# Display.net
KiCad netlist of a schematic drawn in Altium Designer
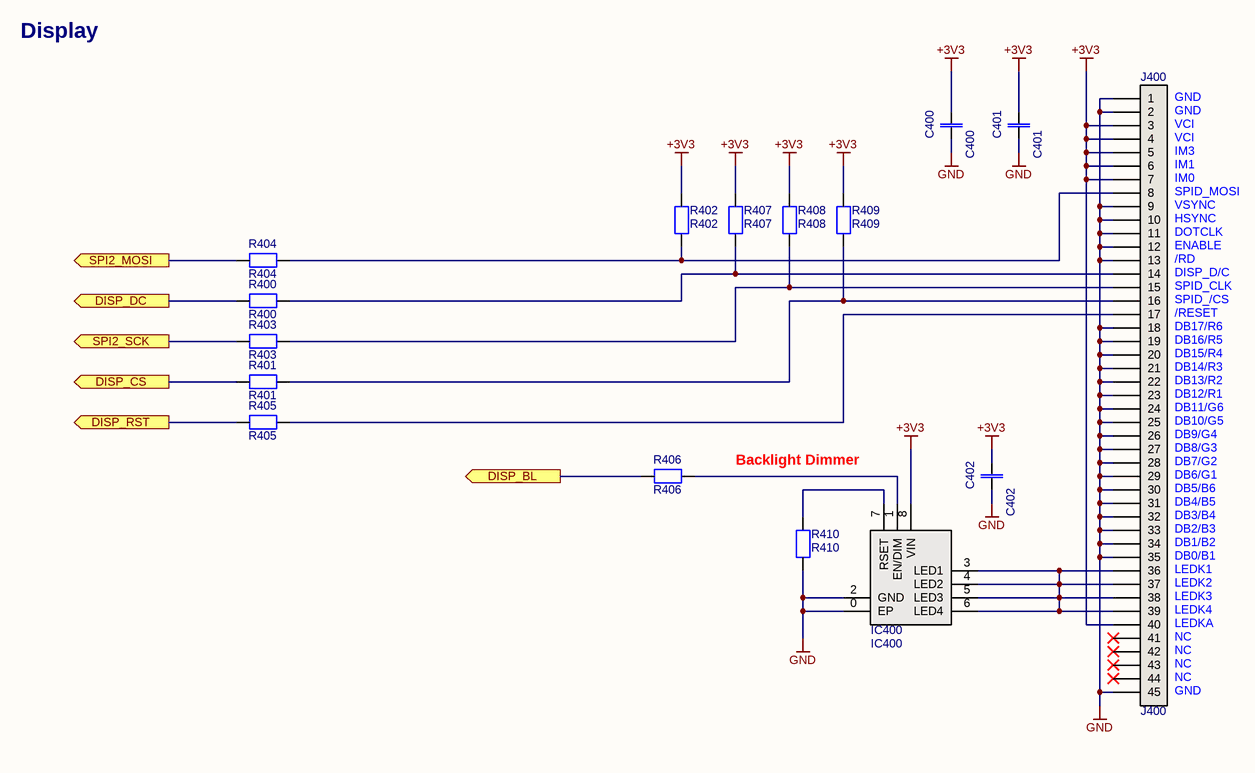
[diagram p0: Display.SchDoc]

(export (version "E")
  (design (tool "Eeschema 10.0.6"))
  (components
    (comp (ref "C400")
      (value "C 1uF 50V")
      (footprint "0805-2012")
      (description "Capacitor")
      (fields
        (field (name "MANUFACTURER") "Murata Electronics North America")
        (field (name "MANUFACTURER PART NUMBER") "GRM21BF51H105ZA12L")
      )
      (libsource (lib "Database_Libs1") (part "Kondensator"))
    )
    (comp (ref "C401")
      (value "C 100nF 50V X7R")
      (footprint "0603-1608")
      (description "Capacitor")
      (fields
        (field (name "MANUFACTURER") "KEMET")
        (field (name "MANUFACTURER PART NUMBER") "C0603C104K5RACTU")
      )
      (libsource (lib "Database_Libs1") (part "Kondensator"))
    )
    (comp (ref "C402")
      (value "C 100nF 50V X7R")
      (footprint "0603-1608")
      (description "Capacitor")
      (fields
        (field (name "MANUFACTURER") "KEMET")
        (field (name "MANUFACTURER PART NUMBER") "C0603C104K5RACTU")
      )
      (libsource (lib "Database_Libs1") (part "Kondensator"))
    )
    (comp (ref "IC400")
      (value "CAT4004AHU2-GT3")
      (footprint "UDFN-8 517AW-01")
      (description "Driver")
      (fields (field (name "MANUFACTURER") "ON Semiconductor") (field (name "VERIFICATION") "18.09.2014 FUW"))
      (libsource (lib "Database_Libs1") (part "CAT4004"))
    )
    (comp (ref "J400")
      (value "FFC 45 Pos F32Q-1A7H1-11045")
      (footprint "SAMTEC_ZF5S-45-01-T-WT")
      (description "Connector")
      (libsource (lib "Database_Libs1") (part "ZIF45 SMD Kontakte"))
    )
    (comp (ref "R400")
      (value "R 100E 1%")
      (footprint "0603-1608")
      (description "Resistor")
      (fields
        (field (name "MANUFACTURER") "Vishay Dale")
        (field (name "MANUFACTURER PART NUMBER") "CRCW0603100RFKEA")
        (field (name "VERIFICATION") "05.07.2012 OPT")
      )
      (libsource (lib "Database_Libs1") (part "Resistor"))
    )
    (comp (ref "R401")
      (value "R 100E 1%")
      (footprint "0603-1608")
      (description "Resistor")
      (fields
        (field (name "MANUFACTURER") "Vishay Dale")
        (field (name "MANUFACTURER PART NUMBER") "CRCW0603100RFKEA")
        (field (name "VERIFICATION") "05.07.2012 OPT")
      )
      (libsource (lib "Database_Libs1") (part "Resistor"))
    )
    (comp (ref "R402")
      (value "R 10k 1%")
      (footprint "0603-1608")
      (description "Resistor")
      (fields
        (field (name "MANUFACTURER") "Vishay Dale")
        (field (name "MANUFACTURER PART NUMBER") "CRCW060310K0FKEAHP")
        (field (name "VERIFICATION") "05.07.2012 OPT")
      )
      (libsource (lib "Database_Libs1") (part "Resistor"))
    )
    (comp (ref "R403")
      (value "R 100E 1%")
      (footprint "0603-1608")
      (description "Resistor")
      (fields
        (field (name "MANUFACTURER") "Vishay Dale")
        (field (name "MANUFACTURER PART NUMBER") "CRCW0603100RFKEA")
        (field (name "VERIFICATION") "05.07.2012 OPT")
      )
      (libsource (lib "Database_Libs1") (part "Resistor"))
    )
    (comp (ref "R404")
      (value "R 100E 1%")
      (footprint "0603-1608")
      (description "Resistor")
      (fields
        (field (name "MANUFACTURER") "Vishay Dale")
        (field (name "MANUFACTURER PART NUMBER") "CRCW0603100RFKEA")
        (field (name "VERIFICATION") "05.07.2012 OPT")
      )
      (libsource (lib "Database_Libs1") (part "Resistor"))
    )
    (comp (ref "R405")
      (value "R 100E 1%")
      (footprint "0603-1608")
      (description "Resistor")
      (fields
        (field (name "MANUFACTURER") "Vishay Dale")
        (field (name "MANUFACTURER PART NUMBER") "CRCW0603100RFKEA")
        (field (name "VERIFICATION") "05.07.2012 OPT")
      )
      (libsource (lib "Database_Libs1") (part "Resistor"))
    )
    (comp (ref "R406")
      (value "R 100E 1%")
      (footprint "0603-1608")
      (description "Resistor")
      (fields
        (field (name "MANUFACTURER") "Vishay Dale")
        (field (name "MANUFACTURER PART NUMBER") "CRCW0603100RFKEA")
        (field (name "VERIFICATION") "05.07.2012 OPT")
      )
      (libsource (lib "Database_Libs1") (part "Resistor"))
    )
    (comp (ref "R407")
      (value "R 10k 1%")
      (footprint "0603-1608")
      (description "Resistor")
      (fields
        (field (name "MANUFACTURER") "Vishay Dale")
        (field (name "MANUFACTURER PART NUMBER") "CRCW060310K0FKEAHP")
        (field (name "VERIFICATION") "05.07.2012 OPT")
      )
      (libsource (lib "Database_Libs1") (part "Resistor"))
    )
    (comp (ref "R408")
      (value "R 10k 1%")
      (footprint "0603-1608")
      (description "Resistor")
      (fields
        (field (name "MANUFACTURER") "Vishay Dale")
        (field (name "MANUFACTURER PART NUMBER") "CRCW060310K0FKEAHP")
        (field (name "VERIFICATION") "05.07.2012 OPT")
      )
      (libsource (lib "Database_Libs1") (part "Resistor"))
    )
    (comp (ref "R409")
      (value "R 10k 1%")
      (footprint "0603-1608")
      (description "Resistor")
      (fields
        (field (name "MANUFACTURER") "Vishay Dale")
        (field (name "MANUFACTURER PART NUMBER") "CRCW060310K0FKEAHP")
        (field (name "VERIFICATION") "05.07.2012 OPT")
      )
      (libsource (lib "Database_Libs1") (part "Resistor"))
    )
    (comp (ref "R410")
      (value "R 3.9k 1%")
      (footprint "0603-1608")
      (description "Resistor")
      (fields
        (field (name "MANUFACTURER") "Vishay Dale")
        (field (name "MANUFACTURER PART NUMBER") "CRCW06033K90FKEA")
        (field (name "VERIFICATION") "05.07.2012 OPT")
      )
      (libsource (lib "Database_Libs1") (part "Resistor"))
    )
  )
  (nets
    (net (code "1") (name "+3V3") (class "Default")
      (node (ref "C400") (pin "1") (pinfunction "1_1") (pintype "passive"))
      (node (ref "C401") (pin "1") (pinfunction "1_1") (pintype "passive"))
      (node (ref "C402") (pin "1") (pinfunction "1_1") (pintype "passive"))
      (node (ref "IC400") (pin "8") (pinfunction "VIN_8") (pintype "passive"))
      (node (ref "J400") (pin "3") (pinfunction "3_3") (pintype "passive"))
      (node (ref "J400") (pin "4") (pinfunction "4_4") (pintype "passive"))
      (node (ref "J400") (pin "40") (pinfunction "40_40") (pintype "passive"))
      (node (ref "J400") (pin "5") (pinfunction "5_5") (pintype "passive"))
      (node (ref "J400") (pin "6") (pinfunction "6_6") (pintype "passive"))
      (node (ref "J400") (pin "7") (pinfunction "7_7") (pintype "passive"))
      (node (ref "R402") (pin "2") (pinfunction "2_2") (pintype "passive"))
      (node (ref "R407") (pin "2") (pinfunction "2_2") (pintype "passive"))
      (node (ref "R408") (pin "2") (pinfunction "2_2") (pintype "passive"))
      (node (ref "R409") (pin "2") (pinfunction "2_2") (pintype "passive"))
    )
    (net (code "2") (name "/DISP_BL") (class "Default")
      (node (ref "R406") (pin "2") (pinfunction "2_2") (pintype "passive"))
    )
    (net (code "3") (name "/DISP_CS") (class "Default")
      (node (ref "R401") (pin "2") (pinfunction "2_2") (pintype "passive"))
    )
    (net (code "4") (name "/DISP_DC") (class "Default")
      (node (ref "R400") (pin "2") (pinfunction "2_2") (pintype "passive"))
    )
    (net (code "5") (name "/DISP_RST") (class "Default")
      (node (ref "R405") (pin "2") (pinfunction "2_2") (pintype "passive"))
    )
    (net (code "6") (name "/SPI2_MOSI") (class "Default")
      (node (ref "R404") (pin "2") (pinfunction "2_2") (pintype "passive"))
    )
    (net (code "7") (name "/SPI2_SCK") (class "Default")
      (node (ref "R403") (pin "2") (pinfunction "2_2") (pintype "passive"))
    )
    (net (code "8") (name "GND") (class "Default")
      (node (ref "C400") (pin "2") (pinfunction "2_2") (pintype "passive"))
      (node (ref "C401") (pin "2") (pinfunction "2_2") (pintype "passive"))
      (node (ref "C402") (pin "2") (pinfunction "2_2") (pintype "passive"))
      (node (ref "IC400") (pin "0") (pinfunction "EP_0") (pintype "passive"))
      (node (ref "IC400") (pin "2") (pinfunction "GND_2") (pintype "passive"))
      (node (ref "J400") (pin "1") (pinfunction "1_1") (pintype "passive"))
      (node (ref "J400") (pin "10") (pinfunction "10_10") (pintype "passive"))
      (node (ref "J400") (pin "11") (pinfunction "11_11") (pintype "passive"))
      (node (ref "J400") (pin "12") (pinfunction "12_12") (pintype "passive"))
      (node (ref "J400") (pin "13") (pinfunction "13_13") (pintype "passive"))
      (node (ref "J400") (pin "18") (pinfunction "18_18") (pintype "passive"))
      (node (ref "J400") (pin "19") (pinfunction "19_19") (pintype "passive"))
      (node (ref "J400") (pin "2") (pinfunction "2_2") (pintype "passive"))
      (node (ref "J400") (pin "20") (pinfunction "20_20") (pintype "passive"))
      (node (ref "J400") (pin "21") (pinfunction "21_21") (pintype "passive"))
      (node (ref "J400") (pin "22") (pinfunction "22_22") (pintype "passive"))
      (node (ref "J400") (pin "23") (pinfunction "23_23") (pintype "passive"))
      (node (ref "J400") (pin "24") (pinfunction "24_24") (pintype "passive"))
      (node (ref "J400") (pin "25") (pinfunction "25_25") (pintype "passive"))
      (node (ref "J400") (pin "26") (pinfunction "26_26") (pintype "passive"))
      (node (ref "J400") (pin "27") (pinfunction "27_27") (pintype "passive"))
      (node (ref "J400") (pin "28") (pinfunction "28_28") (pintype "passive"))
      (node (ref "J400") (pin "29") (pinfunction "29_29") (pintype "passive"))
      (node (ref "J400") (pin "30") (pinfunction "30_30") (pintype "passive"))
      (node (ref "J400") (pin "31") (pinfunction "31_31") (pintype "passive"))
      (node (ref "J400") (pin "32") (pinfunction "32_32") (pintype "passive"))
      (node (ref "J400") (pin "33") (pinfunction "33_33") (pintype "passive"))
      (node (ref "J400") (pin "34") (pinfunction "34_34") (pintype "passive"))
      (node (ref "J400") (pin "35") (pinfunction "35_35") (pintype "passive"))
      (node (ref "J400") (pin "45") (pinfunction "45_45") (pintype "passive"))
      (node (ref "J400") (pin "9") (pinfunction "9_9") (pintype "passive"))
      (node (ref "R410") (pin "2") (pinfunction "2_2") (pintype "passive"))
    )
    (net (code "9") (name "Net-(IC400-EN{slash}DIM)") (class "Default")
      (node (ref "IC400") (pin "1") (pinfunction "EN/DIM_1") (pintype "passive"))
      (node (ref "R406") (pin "1") (pinfunction "1_1") (pintype "passive"))
    )
    (net (code "10") (name "Net-(IC400-LED1)") (class "Default")
      (node (ref "IC400") (pin "3") (pinfunction "LED1_3") (pintype "passive"))
      (node (ref "IC400") (pin "4") (pinfunction "LED2_4") (pintype "passive"))
      (node (ref "IC400") (pin "5") (pinfunction "LED3_5") (pintype "passive"))
      (node (ref "IC400") (pin "6") (pinfunction "LED4_6") (pintype "passive"))
      (node (ref "J400") (pin "36") (pinfunction "36_36") (pintype "passive"))
      (node (ref "J400") (pin "37") (pinfunction "37_37") (pintype "passive"))
      (node (ref "J400") (pin "38") (pinfunction "38_38") (pintype "passive"))
      (node (ref "J400") (pin "39") (pinfunction "39_39") (pintype "passive"))
    )
    (net (code "11") (name "Net-(IC400-RSET)") (class "Default")
      (node (ref "IC400") (pin "7") (pinfunction "RSET_7") (pintype "passive"))
      (node (ref "R410") (pin "1") (pinfunction "1_1") (pintype "passive"))
    )
    (net (code "12") (name "Net-(J400-Pad8)") (class "Default")
      (node (ref "J400") (pin "8") (pinfunction "8_8") (pintype "passive"))
      (node (ref "R402") (pin "1") (pinfunction "1_1") (pintype "passive"))
      (node (ref "R404") (pin "1") (pinfunction "1_1") (pintype "passive"))
    )
    (net (code "13") (name "Net-(J400-Pad14)") (class "Default")
      (node (ref "J400") (pin "14") (pinfunction "14_14") (pintype "passive"))
      (node (ref "R400") (pin "1") (pinfunction "1_1") (pintype "passive"))
      (node (ref "R407") (pin "1") (pinfunction "1_1") (pintype "passive"))
    )
    (net (code "14") (name "Net-(J400-Pad15)") (class "Default")
      (node (ref "J400") (pin "15") (pinfunction "15_15") (pintype "passive"))
      (node (ref "R403") (pin "1") (pinfunction "1_1") (pintype "passive"))
      (node (ref "R408") (pin "1") (pinfunction "1_1") (pintype "passive"))
    )
    (net (code "15") (name "Net-(J400-Pad16)") (class "Default")
      (node (ref "J400") (pin "16") (pinfunction "16_16") (pintype "passive"))
      (node (ref "R401") (pin "1") (pinfunction "1_1") (pintype "passive"))
      (node (ref "R409") (pin "1") (pinfunction "1_1") (pintype "passive"))
    )
    (net (code "16") (name "Net-(J400-Pad17)") (class "Default")
      (node (ref "J400") (pin "17") (pinfunction "17_17") (pintype "passive"))
      (node (ref "R405") (pin "1") (pinfunction "1_1") (pintype "passive"))
    )
    (net (code "17") (name "unconnected-(J400-Pad41)") (class "Default")
      (node (ref "J400") (pin "41") (pinfunction "41_41") (pintype "passive+no_connect"))
    )
    (net (code "18") (name "unconnected-(J400-Pad42)") (class "Default")
      (node (ref "J400") (pin "42") (pinfunction "42_42") (pintype "passive+no_connect"))
    )
    (net (code "19") (name "unconnected-(J400-Pad43)") (class "Default")
      (node (ref "J400") (pin "43") (pinfunction "43_43") (pintype "passive+no_connect"))
    )
    (net (code "20") (name "unconnected-(J400-Pad44)") (class "Default")
      (node (ref "J400") (pin "44") (pinfunction "44_44") (pintype "passive+no_connect"))
    )
  )
)
